# interfaces_module.net
KiCad netlist of a schematic drawn in Altium Designer
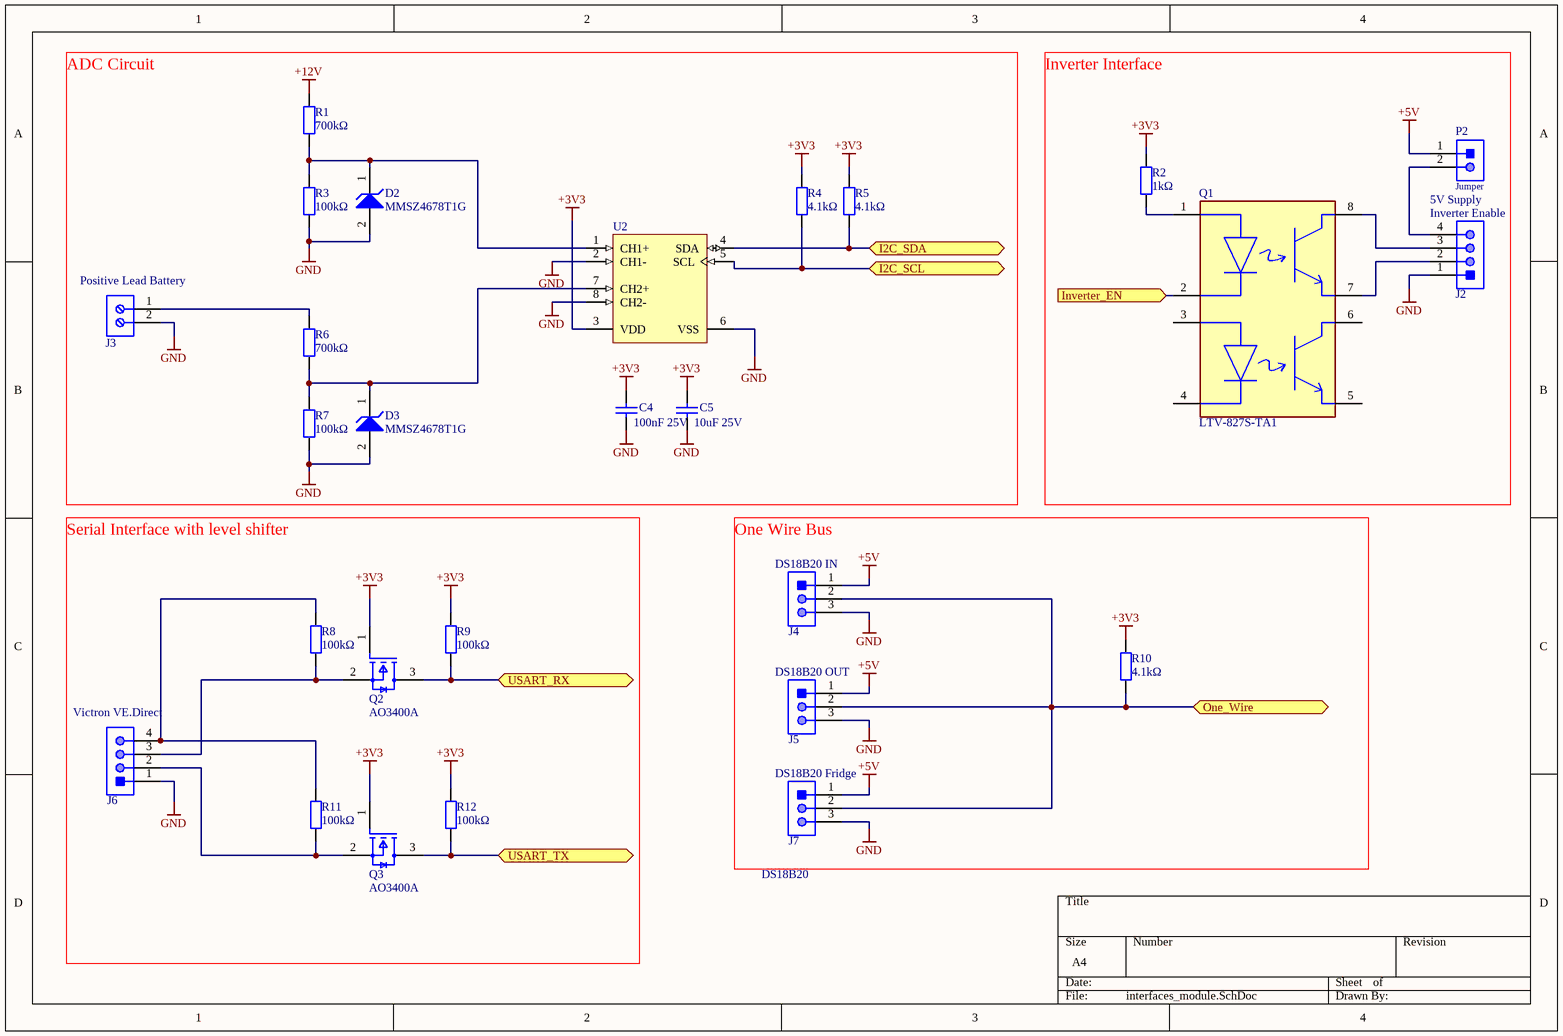
[diagram p0: interfaces_module.SchDoc]

(export (version "E")
  (design (tool "Eeschema 10.0.6"))
  (components
    (comp (ref "C4")
      (value "100nF 25V")
      (footprint "CAPC2013X88X50ML20T25")
      (description "Capacitor")
      (libsource (lib "Schlib") (part "Cap_0805"))
    )
    (comp (ref "C5")
      (value "10uF 25V")
      (footprint "CAPC2013X88X50ML20T25")
      (description "Capacitor")
      (libsource (lib "Schlib") (part "Cap_0805"))
    )
    (comp (ref "D2")
      (value "MMSZ4678T1G")
      (footprint "ONSC-SOD-123-2-425-04_V")
      (description "Zener Voltage Regulator, 500 mW, 2-Pin SOD-123, Pb-Free, Tape and Reel")
      (fields (field (name "MANUFACTURER") "On Semiconductor"))
      (libsource (lib "Altium Content Vault") (part "ONSC-K1A2-2"))
    )
    (comp (ref "D3")
      (value "MMSZ4678T1G")
      (footprint "ONSC-SOD-123-2-425-04_V")
      (description "Zener Voltage Regulator, 500 mW, 2-Pin SOD-123, Pb-Free, Tape and Reel")
      (fields (field (name "MANUFACTURER") "On Semiconductor"))
      (libsource (lib "Altium Content Vault") (part "ONSC-K1A2-2"))
    )
    (comp (ref "J2")
      (value "JST-S4B-PH-SM4-TB-3_V")
      (footprint "JST-S4B-PH-SM4-TB-3_V")
      (libsource (lib "integrated_library") (part "CONNECTOR_JST-S4B-PH-SM4"))
    )
    (comp (ref "J3")
      (value "282836-2")
      (footprint "TECO-282836-2_V")
      (description "Female Header, Pitch 5 mm, 1 x 2 Position, Height 10 mm, Tail Length 3.5 mm, Rohs, Bulk")
      (fields (field (name "VOLTAGE") "300V") (field (name "MANUFACTURER") "TE Connectivity"))
      (libsource (lib "Altium Content Vault") (part "CN-1P-F-TB2"))
    )
    (comp (ref "J4")
      (value "JST-S3B-PH-SM4-TB-3_V")
      (footprint "JST-S3B-PH-SM4-TB-3_V")
      (libsource (lib "integrated_library") (part "CONNECTOR_JST-S3B-PH-SM4"))
    )
    (comp (ref "J5")
      (value "JST-S3B-PH-SM4-TB-3_V")
      (footprint "JST-S3B-PH-SM4-TB-3_V")
      (libsource (lib "integrated_library") (part "CONNECTOR_JST-S3B-PH-SM4"))
    )
    (comp (ref "J6")
      (value "JST-S4B-PH-SM4-TB-3_V")
      (footprint "JST-S4B-PH-SM4-TB-3_V")
      (libsource (lib "") (part "CONNECTOR_JST-S4B-PH-SM4_1"))
    )
    (comp (ref "J7")
      (value "JST-S3B-PH-SM4-TB-3_V")
      (footprint "JST-S3B-PH-SM4-TB-3_V")
      (libsource (lib "integrated_library") (part "CONNECTOR_JST-S3B-PH-SM4"))
    )
    (comp (ref "P2")
      (value "Jumper")
      (footprint "61300211121")
      (description "THT Vertical Pin Header WR-PHD, Pitch 2.54 mm, Single Row, 2 pins")
      (fields
        (field (name "MANUFACTURER") "Wurth Elektronik")
        (field (name "PART NUMBER") "61300211121")
        (field (name "PUBLISHER") "WurthElektronik")
      )
      (libsource (lib "Altium Content Vault") (part "WE-CN-1P-M-R2"))
    )
    (comp (ref "Q1")
      (value "LTV-827S-TA1")
      (footprint "FP-LTV-827S-TA1-MFG")
      (description "OPTOISOLATOR 5KV 2CH TRANS 8-SMD")
      (libsource (lib "Altium Content Vault") (part "7b7d251853f36bb38206e775f4a8ee5"))
    )
    (comp (ref "Q2")
      (value "AO3400A")
      (footprint "SOT-23")
      (description "MOSFET N-CH 30V 5.7A SOT23")
      (libsource (lib "integrated_library") (part "MOSFET_AO3400A"))
    )
    (comp (ref "Q3")
      (value "AO3400A")
      (footprint "SOT-23")
      (description "MOSFET N-CH 30V 5.7A SOT23")
      (libsource (lib "integrated_library") (part "MOSFET_AO3400A"))
    )
    (comp (ref "R1")
      (value "700kΩ")
      (footprint "RESC2013X50X30ML20T20")
      (description "Resistor")
      (libsource (lib "PCB_Project") (part "Res_0805"))
    )
    (comp (ref "R2")
      (value "1kΩ")
      (footprint "RESC2013X50X30ML20T20")
      (description "Resistor")
      (libsource (lib "") (part "Res_0805_2"))
    )
    (comp (ref "R3")
      (value "100kΩ")
      (footprint "RESC2013X50X30ML20T20")
      (description "Resistor")
      (libsource (lib "") (part "Res_0805_1"))
    )
    (comp (ref "R4")
      (value "4.1kΩ")
      (footprint "RESC2013X50X30ML20T20")
      (description "Resistor")
      (libsource (lib "") (part "Res_0805_1"))
    )
    (comp (ref "R5")
      (value "4.1kΩ")
      (footprint "RESC2013X50X30ML20T20")
      (description "Resistor")
      (libsource (lib "") (part "Res_0805_1"))
    )
    (comp (ref "R6")
      (value "700kΩ")
      (footprint "RESC2013X50X30ML20T20")
      (description "Resistor")
      (libsource (lib "PCB_Project") (part "Res_0805"))
    )
    (comp (ref "R7")
      (value "100kΩ")
      (footprint "RESC2013X50X30ML20T20")
      (description "Resistor")
      (libsource (lib "") (part "Res_0805_1"))
    )
    (comp (ref "R8")
      (value "100kΩ")
      (footprint "RESC2013X50X30ML20T20")
      (description "Resistor")
      (libsource (lib "PCB_Project") (part "Res_0805"))
    )
    (comp (ref "R9")
      (value "100kΩ")
      (footprint "RESC2013X50X30ML20T20")
      (description "Resistor")
      (libsource (lib "PCB_Project") (part "Res_0805"))
    )
    (comp (ref "R10")
      (value "4.1kΩ")
      (footprint "RESC2013X50X30ML20T20")
      (description "Resistor")
      (libsource (lib "") (part "Res_0805_1"))
    )
    (comp (ref "R11")
      (value "100kΩ")
      (footprint "RESC2013X50X30ML20T20")
      (description "Resistor")
      (libsource (lib "PCB_Project") (part "Res_0805"))
    )
    (comp (ref "R12")
      (value "100kΩ")
      (footprint "RESC2013X50X30ML20T20")
      (description "Resistor")
      (libsource (lib "PCB_Project") (part "Res_0805"))
    )
    (comp (ref "U2")
      (value "~")
      (footprint "SOIC-SN8_L")
      (libsource (lib "Altium Content Vault") (part "CON-ADC-MCP3426-8"))
    )
  )
  (nets
    (net (code "1") (name "+3V3") (class "Default")
      (node (ref "C4") (pin "2") (pinfunction "2_2") (pintype "passive"))
      (node (ref "C5") (pin "2") (pinfunction "2_2") (pintype "passive"))
      (node (ref "Q2") (pin "1") (pinfunction "G_1") (pintype "passive"))
      (node (ref "Q3") (pin "1") (pinfunction "G_1") (pintype "passive"))
      (node (ref "R10") (pin "2") (pinfunction "2_2") (pintype "passive"))
      (node (ref "R12") (pin "1") (pinfunction "1_1") (pintype "passive"))
      (node (ref "R2") (pin "1") (pinfunction "1_1") (pintype "passive"))
      (node (ref "R4") (pin "2") (pinfunction "2_2") (pintype "passive"))
      (node (ref "R5") (pin "2") (pinfunction "2_2") (pintype "passive"))
      (node (ref "R9") (pin "1") (pinfunction "1_1") (pintype "passive"))
      (node (ref "U2") (pin "3") (pinfunction "VDD_3") (pintype "power_in"))
    )
    (net (code "2") (name "+5V") (class "Default")
      (node (ref "J4") (pin "1") (pinfunction "1_1") (pintype "passive"))
      (node (ref "J5") (pin "1") (pinfunction "1_1") (pintype "passive"))
      (node (ref "J7") (pin "1") (pinfunction "1_1") (pintype "passive"))
      (node (ref "P2") (pin "1") (pinfunction "1_1") (pintype "passive"))
    )
    (net (code "3") (name "+12V") (class "Default")
      (node (ref "R1") (pin "1") (pinfunction "1_1") (pintype "passive"))
    )
    (net (code "4") (name "/I2C_SCL") (class "Default")
      (node (ref "R4") (pin "1") (pinfunction "1_1") (pintype "passive"))
      (node (ref "U2") (pin "5") (pinfunction "SCL_5") (pintype "input"))
    )
    (net (code "5") (name "/I2C_SDA") (class "Default")
      (node (ref "R5") (pin "1") (pinfunction "1_1") (pintype "passive"))
      (node (ref "U2") (pin "4") (pinfunction "SDA_4") (pintype "bidirectional"))
    )
    (net (code "6") (name "/Inverter_EN") (class "Default")
      (node (ref "Q1") (pin "2") (pinfunction "1_Cathode_2") (pintype "passive"))
    )
    (net (code "7") (name "/One_Wire") (class "Default")
      (node (ref "J4") (pin "2") (pinfunction "2_2") (pintype "passive"))
      (node (ref "J5") (pin "2") (pinfunction "2_2") (pintype "passive"))
      (node (ref "J7") (pin "2") (pinfunction "2_2") (pintype "passive"))
      (node (ref "R10") (pin "1") (pinfunction "1_1") (pintype "passive"))
    )
    (net (code "8") (name "/USART_RX") (class "Default")
      (node (ref "Q2") (pin "3") (pinfunction "D_3") (pintype "passive"))
      (node (ref "R9") (pin "2") (pinfunction "2_2") (pintype "passive"))
    )
    (net (code "9") (name "/USART_TX") (class "Default")
      (node (ref "Q3") (pin "3") (pinfunction "D_3") (pintype "passive"))
      (node (ref "R12") (pin "2") (pinfunction "2_2") (pintype "passive"))
    )
    (net (code "10") (name "GND") (class "Default")
      (node (ref "C4") (pin "1") (pinfunction "1_1") (pintype "passive"))
      (node (ref "C5") (pin "1") (pinfunction "1_1") (pintype "passive"))
      (node (ref "D2") (pin "2") (pinfunction "A_2") (pintype "passive"))
      (node (ref "D3") (pin "2") (pinfunction "A_2") (pintype "passive"))
      (node (ref "J2") (pin "1") (pinfunction "1_1") (pintype "passive"))
      (node (ref "J3") (pin "2") (pinfunction "2_2") (pintype "passive"))
      (node (ref "J4") (pin "3") (pinfunction "3_3") (pintype "passive"))
      (node (ref "J5") (pin "3") (pinfunction "3_3") (pintype "passive"))
      (node (ref "J6") (pin "1") (pinfunction "1_1") (pintype "passive"))
      (node (ref "J7") (pin "3") (pinfunction "3_3") (pintype "passive"))
      (node (ref "R3") (pin "1") (pinfunction "1_1") (pintype "passive"))
      (node (ref "R7") (pin "1") (pinfunction "1_1") (pintype "passive"))
      (node (ref "U2") (pin "2") (pinfunction "CH1-_2") (pintype "input"))
      (node (ref "U2") (pin "6") (pinfunction "VSS_6") (pintype "power_in"))
      (node (ref "U2") (pin "8") (pinfunction "CH2-_8") (pintype "input"))
    )
    (net (code "11") (name "Net-(D2-K)") (class "Default")
      (node (ref "D2") (pin "1") (pinfunction "K_1") (pintype "passive"))
      (node (ref "R1") (pin "2") (pinfunction "2_2") (pintype "passive"))
      (node (ref "R3") (pin "2") (pinfunction "2_2") (pintype "passive"))
      (node (ref "U2") (pin "1") (pinfunction "CH1+_1") (pintype "input"))
    )
    (net (code "12") (name "Net-(D3-K)") (class "Default")
      (node (ref "D3") (pin "1") (pinfunction "K_1") (pintype "passive"))
      (node (ref "R6") (pin "2") (pinfunction "2_2") (pintype "passive"))
      (node (ref "R7") (pin "2") (pinfunction "2_2") (pintype "passive"))
      (node (ref "U2") (pin "7") (pinfunction "CH2+_7") (pintype "input"))
    )
    (net (code "13") (name "Net-(J2-Pad2)") (class "Default")
      (node (ref "J2") (pin "2") (pinfunction "2_2") (pintype "passive"))
      (node (ref "Q1") (pin "7") (pinfunction "E_7") (pintype "passive"))
    )
    (net (code "14") (name "Net-(J2-Pad3)") (class "Default")
      (node (ref "J2") (pin "3") (pinfunction "3_3") (pintype "passive"))
      (node (ref "Q1") (pin "8") (pinfunction "C_8") (pintype "passive"))
    )
    (net (code "15") (name "Net-(J2-Pad4)") (class "Default")
      (node (ref "J2") (pin "4") (pinfunction "4_4") (pintype "passive"))
      (node (ref "P2") (pin "2") (pinfunction "2_2") (pintype "passive"))
    )
    (net (code "16") (name "Net-(J3-Pad1)") (class "Default")
      (node (ref "J3") (pin "1") (pinfunction "1_1") (pintype "passive"))
      (node (ref "R6") (pin "1") (pinfunction "1_1") (pintype "passive"))
    )
    (net (code "17") (name "Net-(J6-Pad4)") (class "Default")
      (node (ref "J6") (pin "4") (pinfunction "4_4") (pintype "passive"))
      (node (ref "R11") (pin "1") (pinfunction "1_1") (pintype "passive"))
      (node (ref "R8") (pin "1") (pinfunction "1_1") (pintype "passive"))
    )
    (net (code "18") (name "Net-(Q1-1_Anode)") (class "Default")
      (node (ref "Q1") (pin "1") (pinfunction "1_Anode_1") (pintype "passive"))
      (node (ref "R2") (pin "2") (pinfunction "2_2") (pintype "passive"))
    )
    (net (code "19") (name "Net-(Q2-S)") (class "Default")
      (node (ref "J6") (pin "3") (pinfunction "3_3") (pintype "passive"))
      (node (ref "Q2") (pin "2") (pinfunction "S_2") (pintype "passive"))
      (node (ref "R8") (pin "2") (pinfunction "2_2") (pintype "passive"))
    )
    (net (code "20") (name "Net-(Q3-S)") (class "Default")
      (node (ref "J6") (pin "2") (pinfunction "2_2") (pintype "passive"))
      (node (ref "Q3") (pin "2") (pinfunction "S_2") (pintype "passive"))
      (node (ref "R11") (pin "2") (pinfunction "2_2") (pintype "passive"))
    )
    (net (code "21") (name "unconnected-(Q1-2_Anode-Pad3)") (class "Default")
      (node (ref "Q1") (pin "3") (pinfunction "2_Anode_3") (pintype "passive"))
    )
    (net (code "22") (name "unconnected-(Q1-2_Cathode-Pad4)") (class "Default")
      (node (ref "Q1") (pin "4") (pinfunction "2_Cathode_4") (pintype "passive"))
    )
    (net (code "23") (name "unconnected-(Q1-C-Pad6)") (class "Default")
      (node (ref "Q1") (pin "6") (pinfunction "C_6") (pintype "passive"))
    )
    (net (code "24") (name "unconnected-(Q1-E-Pad5)") (class "Default")
      (node (ref "Q1") (pin "5") (pinfunction "E_5") (pintype "passive"))
    )
  )
)
